# capture_infrarouge.net
KiCad netlist of a schematic drawn in EAGLE
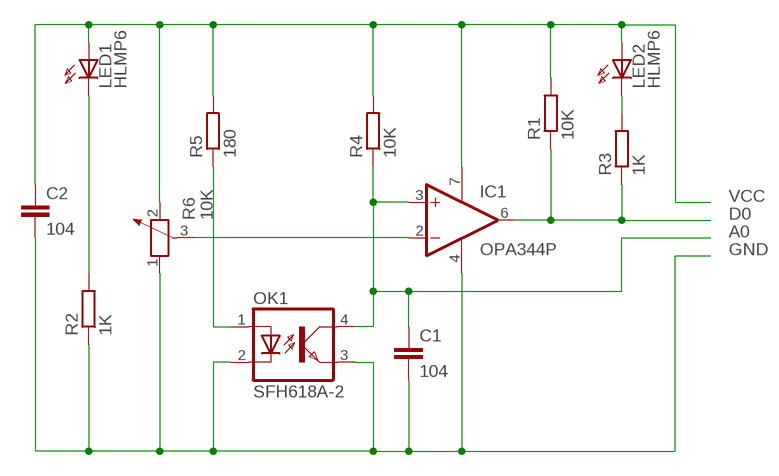
[diagram p0: schematic, sheet 1]

(export (version "E")
  (design (tool "Eeschema 10.0.6"))
  (components
    (comp (ref "C1")
      (value "104")
      (footprint "eagle-import:C025-024X044")
      (libsource (lib "eagle-import") (part "C-EU025-024X044"))
    )
    (comp (ref "C2")
      (value "104")
      (footprint "eagle-import:C025-024X044")
      (libsource (lib "eagle-import") (part "C-EU025-024X044"))
    )
    (comp (ref "IC1")
      (value "OPA344P")
      (footprint "eagle-import:DIL08")
      (libsource (lib "eagle-import") (part "OPAP344"))
    )
    (comp (ref "LED1")
      (value "HLMP6")
      (footprint "eagle-import:HLMP6")
      (fields (field (name "MF") "AGILENT TECHNOLOGIES") (field (name "MPN") "HLMP-6500"))
      (libsource (lib "eagle-import") (part "HLMP6"))
    )
    (comp (ref "LED2")
      (value "HLMP6")
      (footprint "eagle-import:HLMP6")
      (fields (field (name "MF") "AGILENT TECHNOLOGIES") (field (name "MPN") "HLMP-6500"))
      (libsource (lib "eagle-import") (part "HLMP6"))
    )
    (comp (ref "OK1")
      (value "SFH618A-2")
      (footprint "eagle-import:DIP4")
      (fields (field (name "MF") "VISHAY/TELEFUNKEN"))
      (libsource (lib "eagle-import") (part "SFH618?A-2"))
    )
    (comp (ref "R1")
      (value "10K")
      (footprint "eagle-import:0204V")
      (libsource (lib "eagle-import") (part "R-EU_0204/2V"))
    )
    (comp (ref "R2")
      (value "1K")
      (footprint "eagle-import:0204V")
      (libsource (lib "eagle-import") (part "R-EU_0204/2V"))
    )
    (comp (ref "R3")
      (value "1K")
      (footprint "eagle-import:0204V")
      (libsource (lib "eagle-import") (part "R-EU_0204/2V"))
    )
    (comp (ref "R4")
      (value "10K")
      (footprint "eagle-import:0204V")
      (libsource (lib "eagle-import") (part "R-EU_0204/2V"))
    )
    (comp (ref "R5")
      (value "180")
      (footprint "eagle-import:0204V")
      (libsource (lib "eagle-import") (part "R-EU_0204/2V"))
    )
    (comp (ref "R6")
      (value "10K")
      (footprint "eagle-import:PT-10")
      (libsource (lib "eagle-import") (part "POTENTIOMETER_PT-10"))
    )
  )
  (nets
    (net (code "1") (name "/A0") (class "Default")
      (node (ref "C1") (pin "1") (pinfunction "1_1") (pintype "passive"))
      (node (ref "IC1") (pin "3") (pinfunction "+IN_3") (pintype "input"))
      (node (ref "OK1") (pin "4") (pinfunction "COL_4") (pintype "passive"))
      (node (ref "R4") (pin "1") (pinfunction "1_1") (pintype "passive"))
    )
    (net (code "2") (name "/D0") (class "Default")
      (node (ref "IC1") (pin "6") (pinfunction "OUT_6") (pintype "output"))
      (node (ref "R1") (pin "1") (pinfunction "1_1") (pintype "passive"))
      (node (ref "R3") (pin "1") (pinfunction "1_1") (pintype "passive"))
    )
    (net (code "3") (name "/GND") (class "Default")
      (node (ref "C1") (pin "2") (pinfunction "2_2") (pintype "passive"))
      (node (ref "C2") (pin "2") (pinfunction "2_2") (pintype "passive"))
      (node (ref "IC1") (pin "4") (pinfunction "V-_4") (pintype "power_in"))
      (node (ref "OK1") (pin "2") (pinfunction "C_2") (pintype "passive"))
      (node (ref "OK1") (pin "3") (pinfunction "EMIT_3") (pintype "passive"))
      (node (ref "R2") (pin "1") (pinfunction "1_1") (pintype "passive"))
      (node (ref "R6") (pin "1") (pinfunction "1_1") (pintype "passive"))
    )
    (net (code "4") (name "/VCC") (class "Default")
      (node (ref "C2") (pin "1") (pinfunction "1_1") (pintype "passive"))
      (node (ref "IC1") (pin "7") (pinfunction "V+_7") (pintype "power_in"))
      (node (ref "LED1") (pin "A") (pinfunction "A_A") (pintype "passive"))
      (node (ref "LED2") (pin "A") (pinfunction "A_A") (pintype "passive"))
      (node (ref "R1") (pin "2") (pinfunction "2_2") (pintype "passive"))
      (node (ref "R4") (pin "2") (pinfunction "2_2") (pintype "passive"))
      (node (ref "R5") (pin "2") (pinfunction "2_2") (pintype "passive"))
      (node (ref "R6") (pin "2") (pinfunction "2_2") (pintype "passive"))
    )
    (net (code "5") (name "Net-(IC1--IN)") (class "Default")
      (node (ref "IC1") (pin "2") (pinfunction "-IN_2") (pintype "input"))
      (node (ref "R6") (pin "3") (pinfunction "3_3") (pintype "passive"))
    )
    (net (code "6") (name "Net-(LED1-PadK)") (class "Default")
      (node (ref "LED1") (pin "K") (pinfunction "K_K") (pintype "passive"))
      (node (ref "R2") (pin "2") (pinfunction "2_2") (pintype "passive"))
    )
    (net (code "7") (name "Net-(LED2-PadK)") (class "Default")
      (node (ref "LED2") (pin "K") (pinfunction "K_K") (pintype "passive"))
      (node (ref "R3") (pin "2") (pinfunction "2_2") (pintype "passive"))
    )
    (net (code "8") (name "Net-(OK1-A)") (class "Default")
      (node (ref "OK1") (pin "1") (pinfunction "A_1") (pintype "passive"))
      (node (ref "R5") (pin "1") (pinfunction "1_1") (pintype "passive"))
    )
  )
)
